# Strombegrenzung_RevB.net
KiCad netlist of a schematic drawn in EAGLE
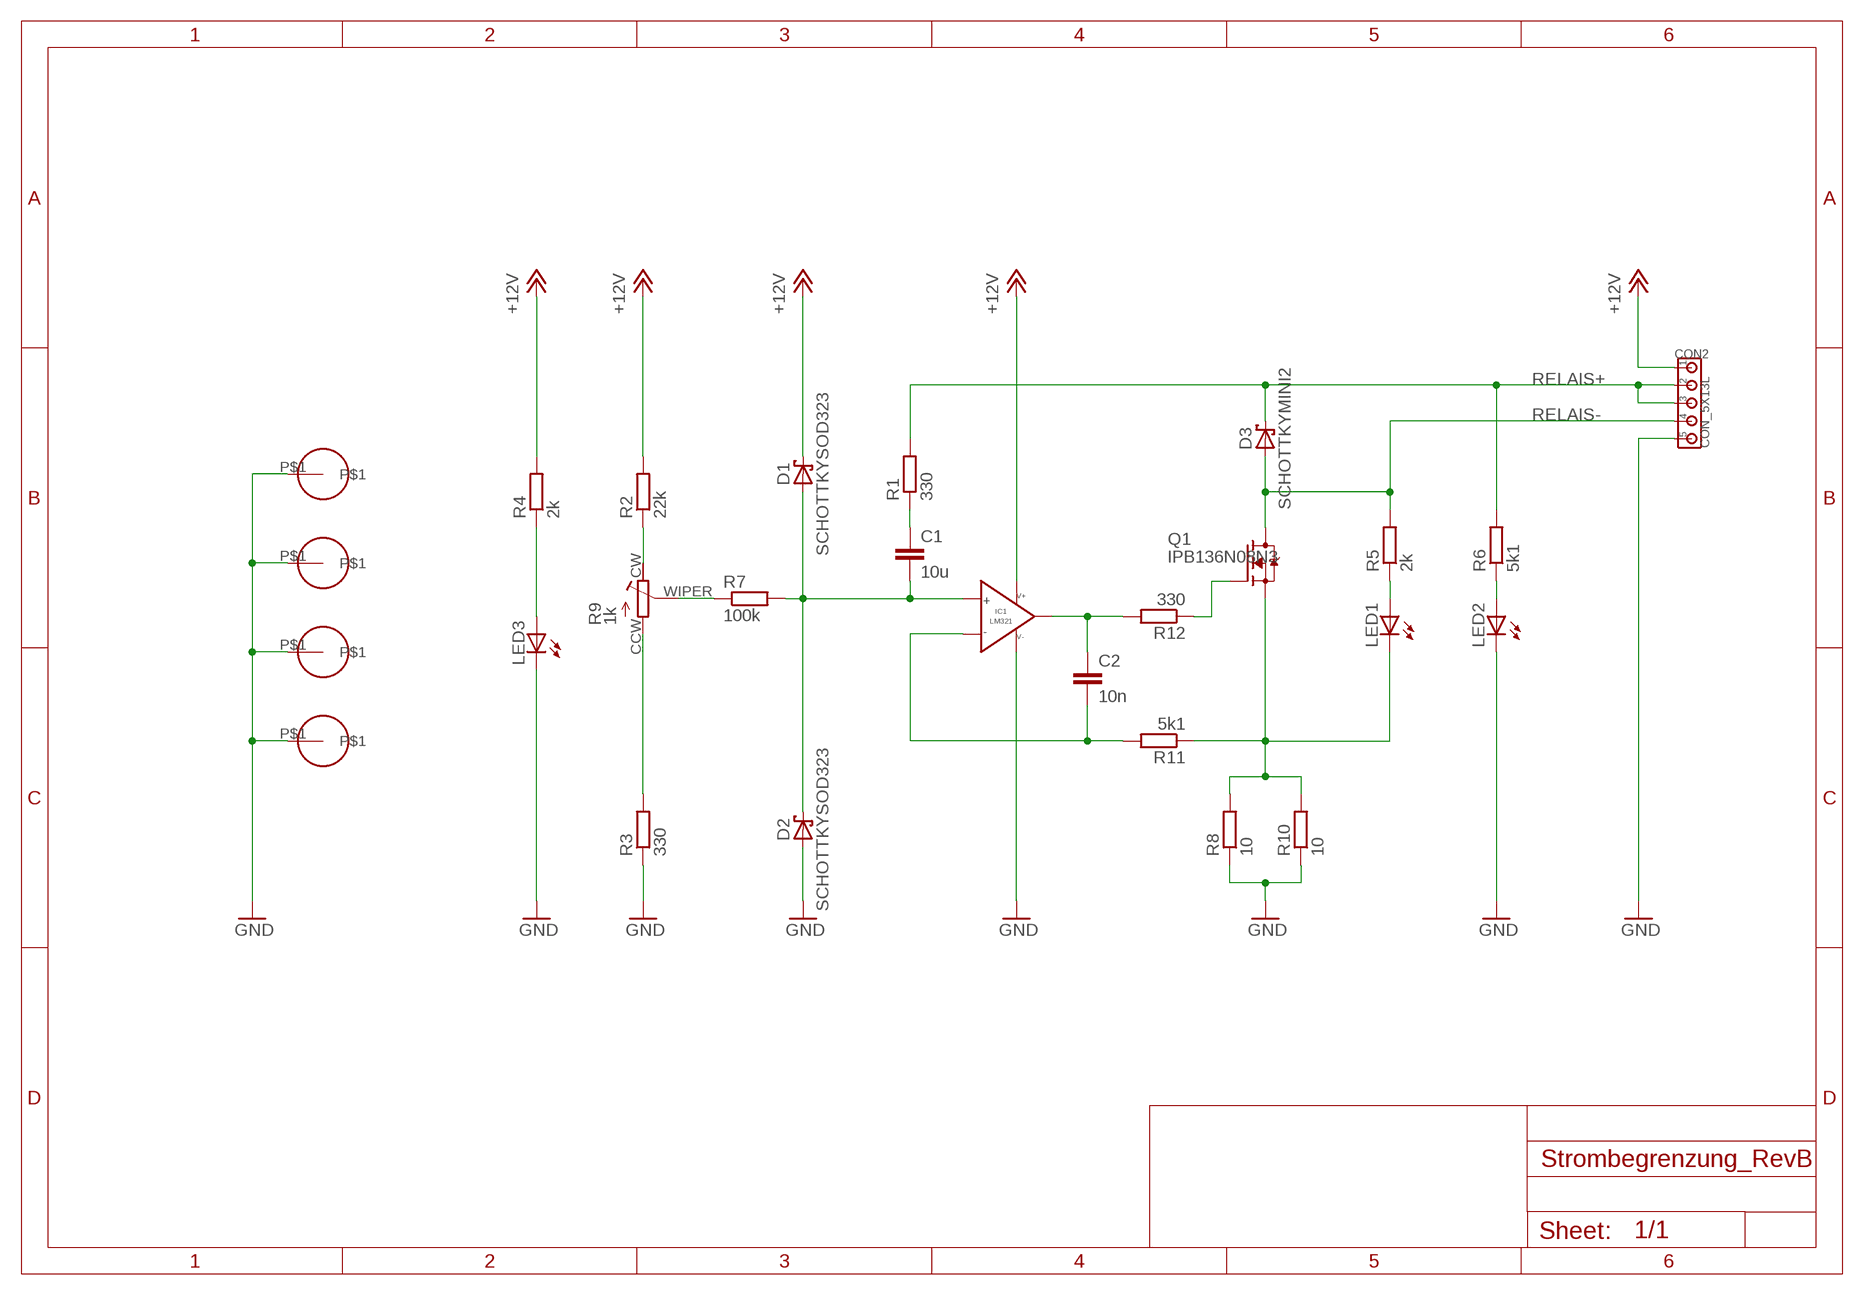
[diagram p0: schematic, sheet 1]

(export (version "E")
  (design (tool "Eeschema 10.0.6"))
  (components
    (comp (ref "C1")
      (value "10u")
      (footprint "eagle-import:C1206")
      (libsource (lib "eagle-import") (part "CC1206"))
    )
    (comp (ref "C2")
      (value "10n")
      (footprint "eagle-import:C0805")
      (libsource (lib "eagle-import") (part "CC0805"))
    )
    (comp (ref "CON2")
      (value "CON_5X13L")
      (footprint "eagle-import:200MIL_5X")
      (libsource (lib "eagle-import") (part "CON_5X13L"))
    )
    (comp (ref "D1")
      (value "SCHOTTKYSOD323")
      (footprint "eagle-import:SOD323")
      (libsource (lib "eagle-import") (part "SCHOTTKYSOD323"))
    )
    (comp (ref "D2")
      (value "SCHOTTKYSOD323")
      (footprint "eagle-import:SOD323")
      (libsource (lib "eagle-import") (part "SCHOTTKYSOD323"))
    )
    (comp (ref "D3")
      (value "SCHOTTKYMINI2")
      (footprint "eagle-import:MINI2-F3-B")
      (libsource (lib "eagle-import") (part "SCHOTTKYMINI2"))
    )
    (comp (ref "IC1")
      (value "LM321")
      (footprint "eagle-import:SOT-23-5")
      (libsource (lib "eagle-import") (part "LM321"))
    )
    (comp (ref "LED1")
      (value "LED0805")
      (footprint "eagle-import:LED0805")
      (libsource (lib "eagle-import") (part "LED0805"))
    )
    (comp (ref "LED2")
      (value "LED0805")
      (footprint "eagle-import:LED0805")
      (libsource (lib "eagle-import") (part "LED0805"))
    )
    (comp (ref "LED3")
      (value "LED0805")
      (footprint "eagle-import:LED0805")
      (libsource (lib "eagle-import") (part "LED0805"))
    )
    (comp (ref "Q1")
      (value "IPB136N08N3")
      (footprint "eagle-import:TO263-3")
      (libsource (lib "eagle-import") (part "N-PWR-MOSFETTO263-3"))
    )
    (comp (ref "R1")
      (value "330")
      (footprint "eagle-import:R0805")
      (libsource (lib "eagle-import") (part "RESISTORR0805"))
    )
    (comp (ref "R2")
      (value "22k")
      (footprint "eagle-import:R0805")
      (libsource (lib "eagle-import") (part "RESISTORR0805"))
    )
    (comp (ref "R3")
      (value "330")
      (footprint "eagle-import:R0805")
      (libsource (lib "eagle-import") (part "RESISTORR0805"))
    )
    (comp (ref "R4")
      (value "2k")
      (footprint "eagle-import:R0805")
      (libsource (lib "eagle-import") (part "RESISTORR0805"))
    )
    (comp (ref "R5")
      (value "2k")
      (footprint "eagle-import:R0805")
      (libsource (lib "eagle-import") (part "RESISTORR0805"))
    )
    (comp (ref "R6")
      (value "5k1")
      (footprint "eagle-import:R0805")
      (libsource (lib "eagle-import") (part "RESISTORR0805"))
    )
    (comp (ref "R7")
      (value "100k")
      (footprint "eagle-import:R0805")
      (libsource (lib "eagle-import") (part "RESISTORR0805"))
    )
    (comp (ref "R8")
      (value "10")
      (footprint "eagle-import:R0805")
      (libsource (lib "eagle-import") (part "RESISTORR0805"))
    )
    (comp (ref "R9")
      (value "1k")
      (footprint "eagle-import:RTRIM3314G")
      (libsource (lib "eagle-import") (part "TRIMMER3314G"))
    )
    (comp (ref "R10")
      (value "10")
      (footprint "eagle-import:R0805")
      (libsource (lib "eagle-import") (part "RESISTORR0805"))
    )
    (comp (ref "R11")
      (value "5k1")
      (footprint "eagle-import:R0805")
      (libsource (lib "eagle-import") (part "RESISTORR0805"))
    )
    (comp (ref "R12")
      (value "330")
      (footprint "eagle-import:R0805")
      (libsource (lib "eagle-import") (part "RESISTORR0805"))
    )
    (comp (ref "U$1")
      (value "HOLE_3.3MM")
      (footprint "eagle-import:HOLE_3.3MM")
      (libsource (lib "eagle-import") (part "HOLE_3.3MM"))
    )
    (comp (ref "U$2")
      (value "HOLE_3.3MM")
      (footprint "eagle-import:HOLE_3.3MM")
      (libsource (lib "eagle-import") (part "HOLE_3.3MM"))
    )
    (comp (ref "U$3")
      (value "HOLE_3.3MM")
      (footprint "eagle-import:HOLE_3.3MM")
      (libsource (lib "eagle-import") (part "HOLE_3.3MM"))
    )
    (comp (ref "U$4")
      (value "HOLE_3.3MM")
      (footprint "eagle-import:HOLE_3.3MM")
      (libsource (lib "eagle-import") (part "HOLE_3.3MM"))
    )
  )
  (nets
    (net (code "1") (name "+12V") (class "Default")
      (node (ref "CON2") (pin "1") (pinfunction "1_1") (pintype "passive"))
      (node (ref "D1") (pin "C") (pinfunction "C_C") (pintype "passive"))
      (node (ref "IC1") (pin "5") (pinfunction "V+_5") (pintype "input"))
      (node (ref "R2") (pin "2") (pinfunction "2_2") (pintype "passive"))
      (node (ref "R4") (pin "2") (pinfunction "2_2") (pintype "passive"))
    )
    (net (code "2") (name "/RELAIS+") (class "Default")
      (node (ref "CON2") (pin "2") (pinfunction "2_2") (pintype "passive"))
      (node (ref "CON2") (pin "3") (pinfunction "3_3") (pintype "passive"))
      (node (ref "D3") (pin "C") (pinfunction "C_C") (pintype "passive"))
      (node (ref "R1") (pin "2") (pinfunction "2_2") (pintype "passive"))
      (node (ref "R6") (pin "2") (pinfunction "2_2") (pintype "passive"))
    )
    (net (code "3") (name "/RELAIS-") (class "Default")
      (node (ref "CON2") (pin "4") (pinfunction "4_4") (pintype "passive"))
      (node (ref "D3") (pin "A") (pinfunction "A_A") (pintype "passive"))
      (node (ref "Q1") (pin "TAB") (pinfunction "D_TAB") (pintype "passive"))
      (node (ref "R5") (pin "2") (pinfunction "2_2") (pintype "passive"))
    )
    (net (code "4") (name "GND") (class "Default")
      (node (ref "CON2") (pin "5") (pinfunction "5_5") (pintype "passive"))
      (node (ref "D2") (pin "A") (pinfunction "A_A") (pintype "passive"))
      (node (ref "IC1") (pin "2") (pinfunction "V-_2") (pintype "input"))
      (node (ref "LED2") (pin "C") (pinfunction "C_C") (pintype "passive"))
      (node (ref "LED3") (pin "C") (pinfunction "C_C") (pintype "passive"))
      (node (ref "R10") (pin "1") (pinfunction "1_1") (pintype "passive"))
      (node (ref "R3") (pin "1") (pinfunction "1_1") (pintype "passive"))
      (node (ref "R8") (pin "1") (pinfunction "1_1") (pintype "passive"))
      (node (ref "U$1") (pin "P$1") (pinfunction "P$1_P$1") (pintype "bidirectional"))
      (node (ref "U$2") (pin "P$1") (pinfunction "P$1_P$1") (pintype "bidirectional"))
      (node (ref "U$3") (pin "P$1") (pinfunction "P$1_P$1") (pintype "bidirectional"))
      (node (ref "U$4") (pin "P$1") (pinfunction "P$1_P$1") (pintype "bidirectional"))
    )
    (net (code "5") (name "Net-(C1-Pad1)") (class "Default")
      (node (ref "C1") (pin "1") (pinfunction "1_1") (pintype "passive"))
      (node (ref "R1") (pin "1") (pinfunction "1_1") (pintype "passive"))
    )
    (net (code "6") (name "Net-(IC1-IN+)") (class "Default")
      (node (ref "C1") (pin "2") (pinfunction "2_2") (pintype "passive"))
      (node (ref "D1") (pin "A") (pinfunction "A_A") (pintype "passive"))
      (node (ref "D2") (pin "C") (pinfunction "C_C") (pintype "passive"))
      (node (ref "IC1") (pin "1") (pinfunction "IN+_1") (pintype "input"))
      (node (ref "R7") (pin "2") (pinfunction "2_2") (pintype "passive"))
    )
    (net (code "7") (name "Net-(IC1-IN-)") (class "Default")
      (node (ref "C2") (pin "2") (pinfunction "2_2") (pintype "passive"))
      (node (ref "IC1") (pin "3") (pinfunction "IN-_3") (pintype "input"))
      (node (ref "R11") (pin "2") (pinfunction "2_2") (pintype "passive"))
    )
    (net (code "8") (name "Net-(IC1-VOUT)") (class "Default")
      (node (ref "C2") (pin "1") (pinfunction "1_1") (pintype "passive"))
      (node (ref "IC1") (pin "4") (pinfunction "VOUT_4") (pintype "output"))
      (node (ref "R12") (pin "2") (pinfunction "2_2") (pintype "passive"))
    )
    (net (code "9") (name "Net-(LED1-PadA)") (class "Default")
      (node (ref "LED1") (pin "A") (pinfunction "A_A") (pintype "passive"))
      (node (ref "R5") (pin "1") (pinfunction "1_1") (pintype "passive"))
    )
    (net (code "10") (name "Net-(LED2-PadA)") (class "Default")
      (node (ref "LED2") (pin "A") (pinfunction "A_A") (pintype "passive"))
      (node (ref "R6") (pin "1") (pinfunction "1_1") (pintype "passive"))
    )
    (net (code "11") (name "Net-(LED3-PadA)") (class "Default")
      (node (ref "LED3") (pin "A") (pinfunction "A_A") (pintype "passive"))
      (node (ref "R4") (pin "1") (pinfunction "1_1") (pintype "passive"))
    )
    (net (code "12") (name "Net-(Q1-G)") (class "Default")
      (node (ref "Q1") (pin "1") (pinfunction "G_1") (pintype "passive"))
      (node (ref "R12") (pin "1") (pinfunction "1_1") (pintype "passive"))
    )
    (net (code "13") (name "Net-(Q1-S)") (class "Default")
      (node (ref "LED1") (pin "C") (pinfunction "C_C") (pintype "passive"))
      (node (ref "Q1") (pin "3") (pinfunction "S_3") (pintype "passive"))
      (node (ref "R10") (pin "2") (pinfunction "2_2") (pintype "passive"))
      (node (ref "R11") (pin "1") (pinfunction "1_1") (pintype "passive"))
      (node (ref "R8") (pin "2") (pinfunction "2_2") (pintype "passive"))
    )
    (net (code "14") (name "Net-(R2-Pad1)") (class "Default")
      (node (ref "R2") (pin "1") (pinfunction "1_1") (pintype "passive"))
      (node (ref "R9") (pin "CW") (pinfunction "CW_CW") (pintype "passive"))
    )
    (net (code "15") (name "Net-(R3-Pad2)") (class "Default")
      (node (ref "R3") (pin "2") (pinfunction "2_2") (pintype "passive"))
      (node (ref "R9") (pin "CCW") (pinfunction "CCW_CCW") (pintype "passive"))
    )
    (net (code "16") (name "Net-(R7-Pad1)") (class "Default")
      (node (ref "R7") (pin "1") (pinfunction "1_1") (pintype "passive"))
      (node (ref "R9") (pin "WIPER") (pinfunction "WIPER_WIPER") (pintype "passive"))
    )
  )
)
